# Motor_Driver.net
KiCad netlist of a schematic drawn in Altium Designer
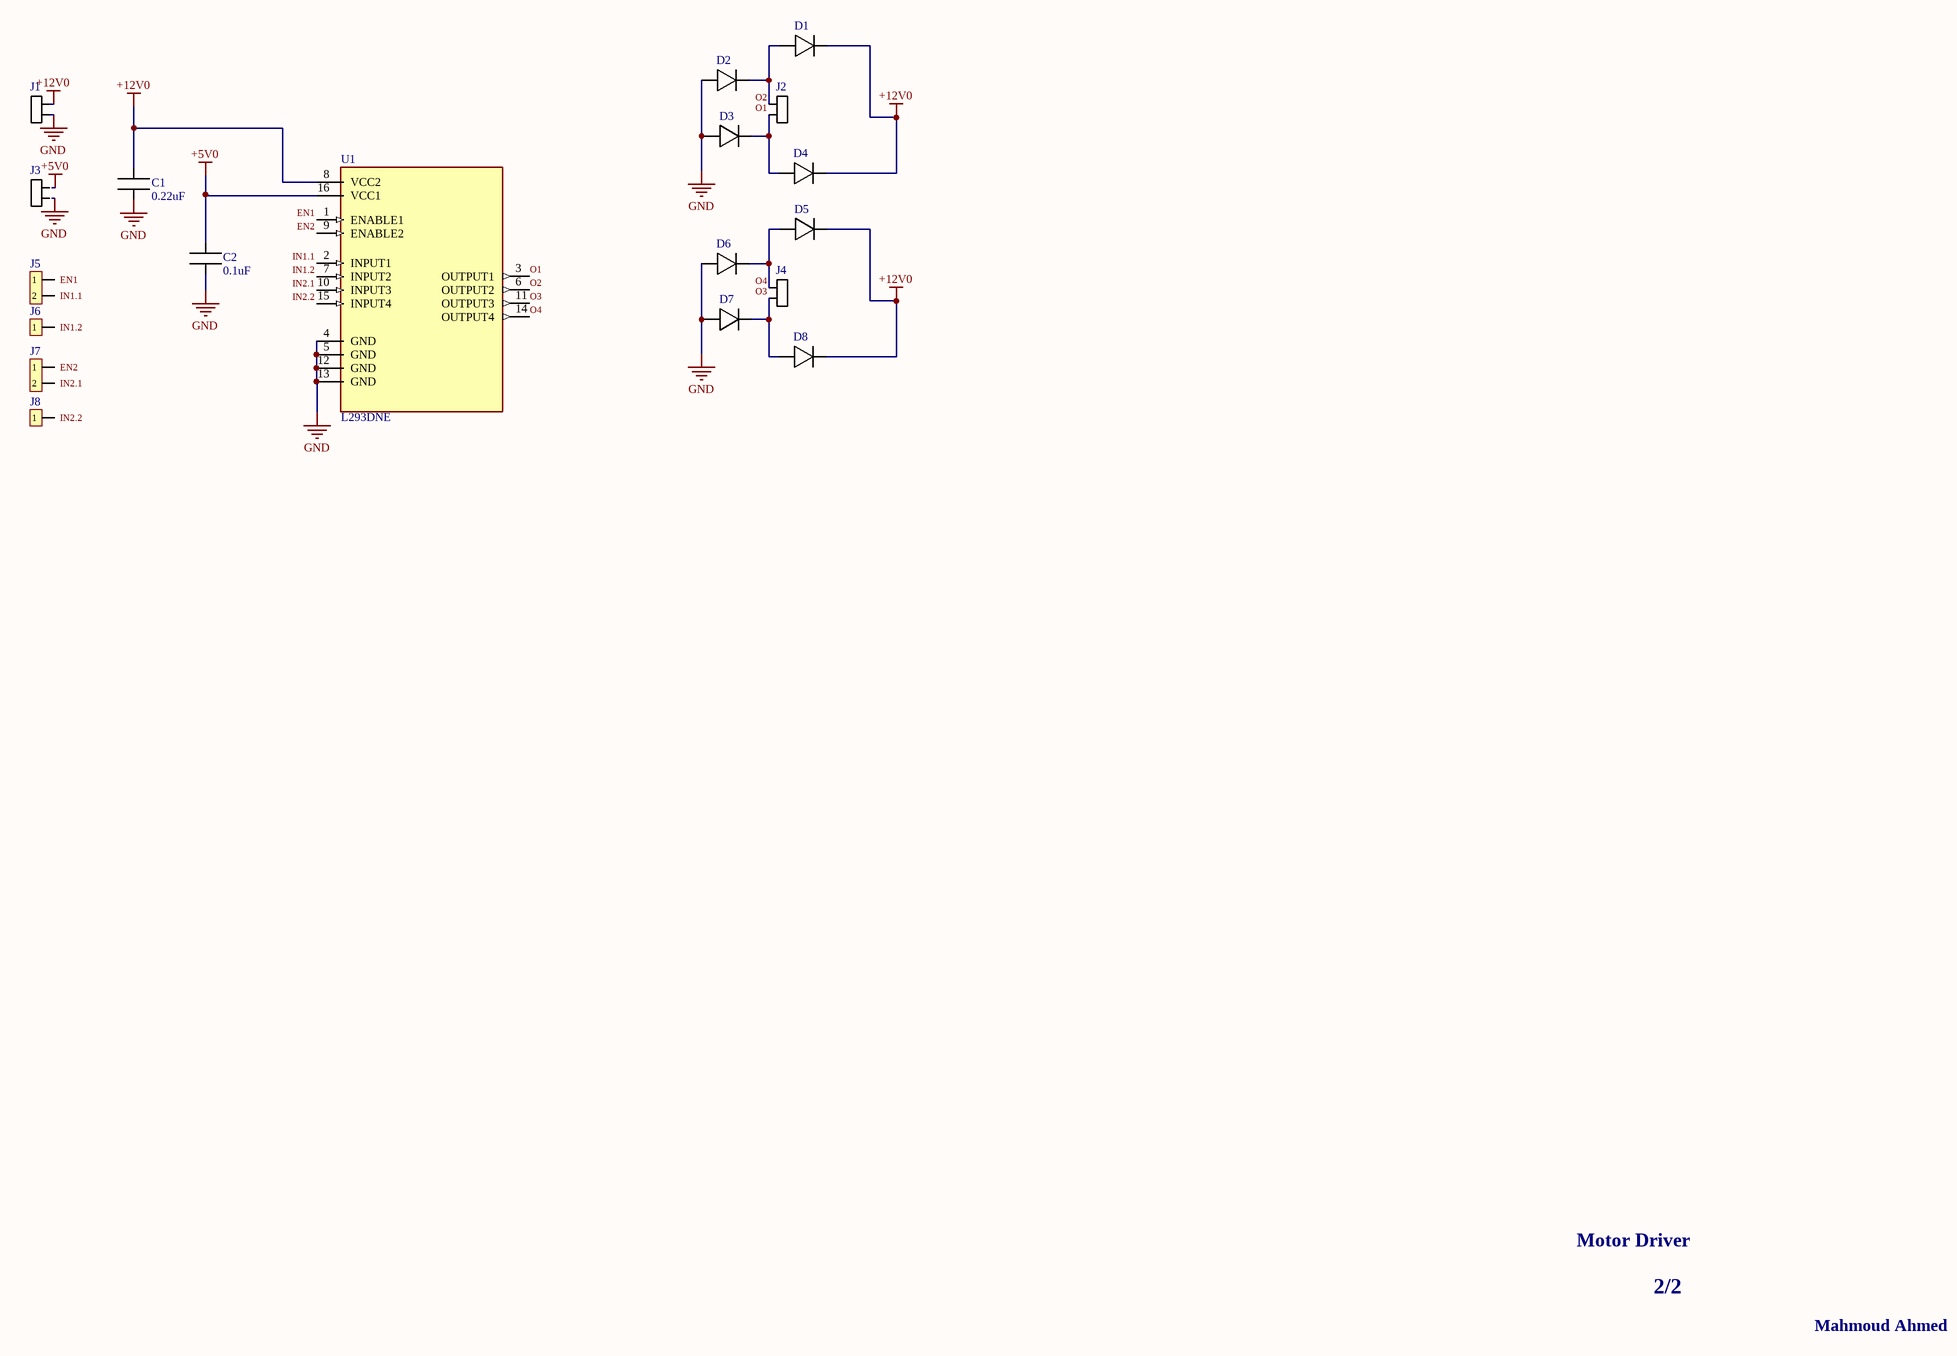
[diagram p0: Motor Driver.SchDoc]

(export (version "E")
  (design (tool "Eeschema 10.0.6"))
  (components
    (comp (ref "C1")
      (value "0.22uF")
      (footprint "C0805")
      (description "CAP CER 0.22UF 25V X7R 0805")
      (fields (field (name "MPN") "CC0805KRX7R8BB224") (field (name "MANUFACTURER") "YAGEO"))
      (libsource (lib "Microcontroller circuit") (part "0.22uF CAP"))
    )
    (comp (ref "C2")
      (value "0.1uF")
      (footprint "C0805")
      (description "CAP CER 0.1UF 50V X7R 0805")
      (fields (field (name "MANUFACTURER") "TDK Corporation") (field (name "MPN") "C2012X7R1H104K085AA"))
      (libsource (lib "Microcontroller circuit") (part "0.1uF CAP"))
    )
    (comp (ref "D1")
      (value "1N4007G")
      (footprint "1N4007")
      (description "DIODE GEN PURP 1A DO204AL")
      (fields (field (name "MANUFACTURER") "Taiwan Semiconductor Corporation"))
      (libsource (lib "Microcontroller circuit") (part "1N4007"))
    )
    (comp (ref "D2")
      (value "1N4007G")
      (footprint "1N4007")
      (description "DIODE GEN PURP 1A DO204AL")
      (fields (field (name "MANUFACTURER") "Taiwan Semiconductor Corporation"))
      (libsource (lib "Microcontroller circuit") (part "1N4007"))
    )
    (comp (ref "D3")
      (value "1N4007G")
      (footprint "1N4007")
      (description "DIODE GEN PURP 1A DO204AL")
      (fields (field (name "MANUFACTURER") "Taiwan Semiconductor Corporation"))
      (libsource (lib "Microcontroller circuit") (part "1N4007"))
    )
    (comp (ref "D4")
      (value "1N4007G")
      (footprint "1N4007")
      (description "DIODE GEN PURP 1A DO204AL")
      (fields (field (name "MANUFACTURER") "Taiwan Semiconductor Corporation"))
      (libsource (lib "Microcontroller circuit") (part "1N4007"))
    )
    (comp (ref "D5")
      (value "1N4007G")
      (footprint "1N4007")
      (description "DIODE GEN PURP 1A DO204AL")
      (fields (field (name "MANUFACTURER") "Taiwan Semiconductor Corporation"))
      (libsource (lib "Microcontroller circuit") (part "1N4007"))
    )
    (comp (ref "D6")
      (value "1N4007G")
      (footprint "1N4007")
      (description "DIODE GEN PURP 1A DO204AL")
      (fields (field (name "MANUFACTURER") "Taiwan Semiconductor Corporation"))
      (libsource (lib "Microcontroller circuit") (part "1N4007"))
    )
    (comp (ref "D7")
      (value "1N4007G")
      (footprint "1N4007")
      (description "DIODE GEN PURP 1A DO204AL")
      (fields (field (name "MANUFACTURER") "Taiwan Semiconductor Corporation"))
      (libsource (lib "Microcontroller circuit") (part "1N4007"))
    )
    (comp (ref "D8")
      (value "1N4007G")
      (footprint "1N4007")
      (description "DIODE GEN PURP 1A DO204AL")
      (fields (field (name "MANUFACTURER") "Taiwan Semiconductor Corporation"))
      (libsource (lib "Microcontroller circuit") (part "1N4007"))
    )
    (comp (ref "J1")
      (value "102-6179-ND")
      (footprint "Terminal block")
      (description "TERMINAL BLOCK, SCREW TYPE, 5.08")
      (fields (field (name "MPN") "TB004-508-02BE") (field (name "MANUFACTURER") "CUI Devices"))
      (libsource (lib "Microcontroller circuit") (part "Terminal block"))
    )
    (comp (ref "J2")
      (value "102-6179-ND")
      (footprint "Terminal block")
      (description "TERMINAL BLOCK, SCREW TYPE, 5.08")
      (fields (field (name "MPN") "TB004-508-02BE") (field (name "MANUFACTURER") "CUI Devices"))
      (libsource (lib "Microcontroller circuit") (part "Terminal block"))
    )
    (comp (ref "J3")
      (value "102-6179-ND")
      (footprint "Terminal block")
      (description "TERMINAL BLOCK, SCREW TYPE, 5.08")
      (fields (field (name "MPN") "TB004-508-02BE") (field (name "MANUFACTURER") "CUI Devices"))
      (libsource (lib "Microcontroller circuit") (part "Terminal block"))
    )
    (comp (ref "J4")
      (value "102-6179-ND")
      (footprint "Terminal block")
      (description "TERMINAL BLOCK, SCREW TYPE, 5.08")
      (fields (field (name "MPN") "TB004-508-02BE") (field (name "MANUFACTURER") "CUI Devices"))
      (libsource (lib "Microcontroller circuit") (part "Terminal block"))
    )
    (comp (ref "J5")
      (value "68000-202HLF")
      (footprint "HDR 1x2M")
      (description "CONN HEADER VERT 2POS 2.54MM")
      (fields (field (name "MANUFACTURER") "Amphenol ICC (FCI)"))
      (libsource (lib "Microcontroller circuit") (part "HDR 1x2M"))
    )
    (comp (ref "J6")
      (value "PH1-01-UA")
      (footprint "HDR 1x1M")
      (description "CONN HEADER VERT 1POS 2.54MM")
      (fields (field (name "MANUFACTURER") "Adam Tech"))
      (libsource (lib "Microcontroller circuit") (part "HDR 1x1M"))
    )
    (comp (ref "J7")
      (value "68000-202HLF")
      (footprint "HDR 1x2M")
      (description "CONN HEADER VERT 2POS 2.54MM")
      (fields (field (name "MANUFACTURER") "Amphenol ICC (FCI)"))
      (libsource (lib "Microcontroller circuit") (part "HDR 1x2M"))
    )
    (comp (ref "J8")
      (value "PH1-01-UA")
      (footprint "HDR 1x1M")
      (description "CONN HEADER VERT 1POS 2.54MM")
      (fields (field (name "MANUFACTURER") "Adam Tech"))
      (libsource (lib "Microcontroller circuit") (part "HDR 1x1M"))
    )
    (comp (ref "U1")
      (value "L293DNE")
      (footprint "L293D")
      (description "IC MTR DRV BIPOLAR 4.5-36V 16DIP")
      (fields (field (name "MANUFACTURER") "Texas Instruments"))
      (libsource (lib "Microcontroller circuit") (part "L293DNE"))
    )
  )
  (nets
    (net (code "1") (name "+5V0") (class "Default")
      (node (ref "C2") (pin "2") (pinfunction "2_2") (pintype "passive"))
      (node (ref "U1") (pin "16") (pinfunction "VCC1_16") (pintype "power_in"))
    )
    (net (code "2") (name "+12V0") (class "Default")
      (node (ref "C1") (pin "2") (pinfunction "2_2") (pintype "passive"))
      (node (ref "D1") (pin "1") (pinfunction "cathode_1") (pintype "passive"))
      (node (ref "D4") (pin "1") (pinfunction "cathode_1") (pintype "passive"))
      (node (ref "D5") (pin "1") (pinfunction "cathode_1") (pintype "passive"))
      (node (ref "D8") (pin "1") (pinfunction "cathode_1") (pintype "passive"))
      (node (ref "J1") (pin "1") (pinfunction "*_1") (pintype "passive"))
      (node (ref "U1") (pin "8") (pinfunction "VCC2_8") (pintype "power_in"))
    )
    (net (code "3") (name "/EN1") (class "Default")
      (node (ref "U1") (pin "1") (pinfunction "ENABLE1_1") (pintype "input"))
    )
    (net (code "4") (name "/EN2") (class "Default")
      (node (ref "U1") (pin "9") (pinfunction "ENABLE2_9") (pintype "input"))
    )
    (net (code "5") (name "/IN1.1") (class "Default")
      (node (ref "U1") (pin "2") (pinfunction "INPUT1_2") (pintype "input"))
    )
    (net (code "6") (name "/IN1.2") (class "Default")
      (node (ref "U1") (pin "7") (pinfunction "INPUT2_7") (pintype "input"))
    )
    (net (code "7") (name "/IN2.1") (class "Default")
      (node (ref "U1") (pin "10") (pinfunction "INPUT3_10") (pintype "input"))
    )
    (net (code "8") (name "/IN2.2") (class "Default")
      (node (ref "U1") (pin "15") (pinfunction "INPUT4_15") (pintype "input"))
    )
    (net (code "9") (name "/O1") (class "Default")
      (node (ref "D3") (pin "1") (pinfunction "cathode_1") (pintype "passive"))
      (node (ref "D4") (pin "2") (pinfunction "Anode_2") (pintype "passive"))
      (node (ref "J2") (pin "2") (pinfunction "*_2") (pintype "passive"))
      (node (ref "U1") (pin "3") (pinfunction "OUTPUT1_3") (pintype "output"))
    )
    (net (code "10") (name "/O2") (class "Default")
      (node (ref "D1") (pin "2") (pinfunction "Anode_2") (pintype "passive"))
      (node (ref "D2") (pin "1") (pinfunction "cathode_1") (pintype "passive"))
      (node (ref "J2") (pin "1") (pinfunction "*_1") (pintype "passive"))
      (node (ref "U1") (pin "6") (pinfunction "OUTPUT2_6") (pintype "output"))
    )
    (net (code "11") (name "/O3") (class "Default")
      (node (ref "D7") (pin "1") (pinfunction "cathode_1") (pintype "passive"))
      (node (ref "D8") (pin "2") (pinfunction "Anode_2") (pintype "passive"))
      (node (ref "J4") (pin "2") (pinfunction "*_2") (pintype "passive"))
      (node (ref "U1") (pin "11") (pinfunction "OUTPUT3_11") (pintype "output"))
    )
    (net (code "12") (name "/O4") (class "Default")
      (node (ref "D5") (pin "2") (pinfunction "Anode_2") (pintype "passive"))
      (node (ref "D6") (pin "1") (pinfunction "cathode_1") (pintype "passive"))
      (node (ref "J4") (pin "1") (pinfunction "*_1") (pintype "passive"))
      (node (ref "U1") (pin "14") (pinfunction "OUTPUT4_14") (pintype "output"))
    )
    (net (code "13") (name "GND") (class "Default")
      (node (ref "C1") (pin "1") (pinfunction "1_1") (pintype "passive"))
      (node (ref "C2") (pin "1") (pinfunction "1_1") (pintype "passive"))
      (node (ref "D2") (pin "2") (pinfunction "Anode_2") (pintype "passive"))
      (node (ref "D3") (pin "2") (pinfunction "Anode_2") (pintype "passive"))
      (node (ref "D6") (pin "2") (pinfunction "Anode_2") (pintype "passive"))
      (node (ref "D7") (pin "2") (pinfunction "Anode_2") (pintype "passive"))
      (node (ref "J1") (pin "2") (pinfunction "*_2") (pintype "passive"))
      (node (ref "U1") (pin "12") (pinfunction "GND_12") (pintype "power_in"))
      (node (ref "U1") (pin "13") (pinfunction "GND_13") (pintype "power_in"))
      (node (ref "U1") (pin "4") (pinfunction "GND_4") (pintype "power_in"))
      (node (ref "U1") (pin "5") (pinfunction "GND_5") (pintype "power_in"))
    )
    (net (code "14") (name "unconnected-(J3-*-Pad1)") (class "Default")
      (node (ref "J3") (pin "1") (pinfunction "*_1") (pintype "passive"))
    )
    (net (code "15") (name "unconnected-(J3-*-Pad2)") (class "Default")
      (node (ref "J3") (pin "2") (pinfunction "*_2") (pintype "passive"))
    )
    (net (code "16") (name "unconnected-(J5-Pad1)") (class "Default")
      (node (ref "J5") (pin "1") (pinfunction "1_1") (pintype "passive"))
    )
    (net (code "17") (name "unconnected-(J5-Pad2)") (class "Default")
      (node (ref "J5") (pin "2") (pinfunction "2_2") (pintype "passive"))
    )
    (net (code "18") (name "unconnected-(J6-Pad1)") (class "Default")
      (node (ref "J6") (pin "1") (pinfunction "1_1") (pintype "passive"))
    )
    (net (code "19") (name "unconnected-(J7-Pad1)") (class "Default")
      (node (ref "J7") (pin "1") (pinfunction "1_1") (pintype "passive"))
    )
    (net (code "20") (name "unconnected-(J7-Pad2)") (class "Default")
      (node (ref "J7") (pin "2") (pinfunction "2_2") (pintype "passive"))
    )
    (net (code "21") (name "unconnected-(J8-Pad1)") (class "Default")
      (node (ref "J8") (pin "1") (pinfunction "1_1") (pintype "passive"))
    )
  )
)
